# tree.net
KiCad netlist of a schematic drawn in EAGLE
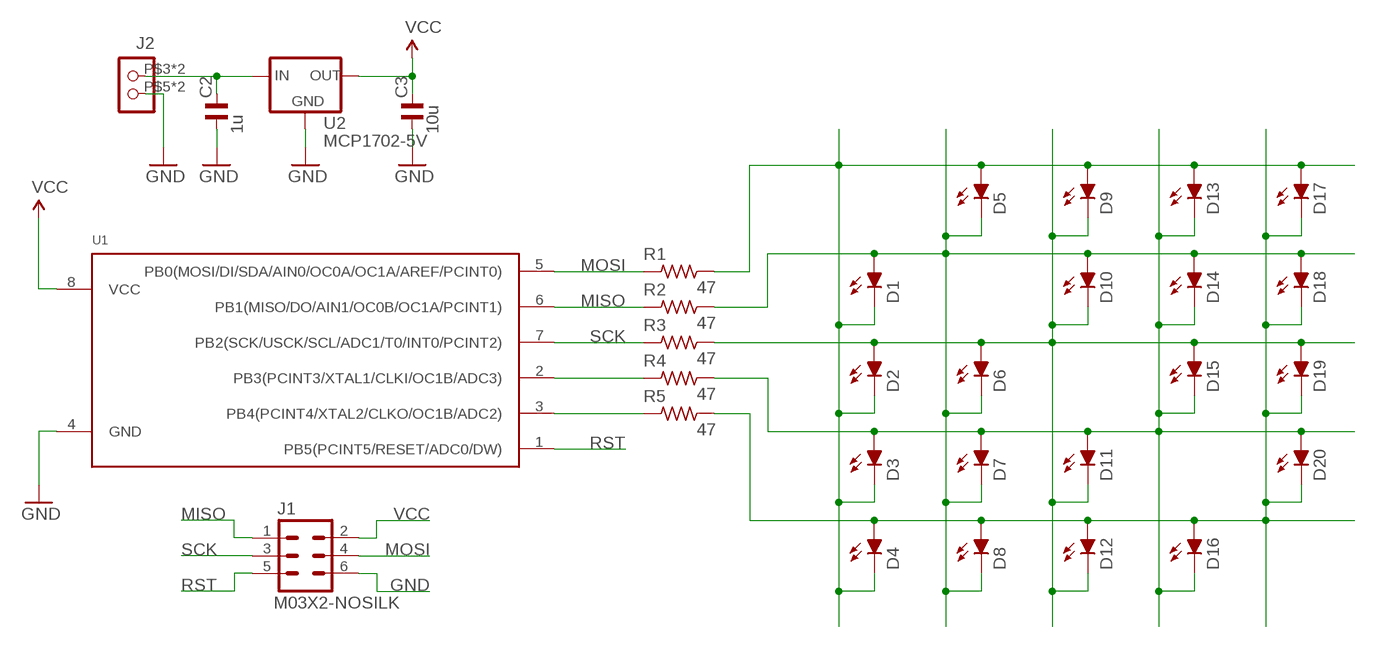
[diagram p0: schematic, sheet 1]

(export (version "E")
  (design (tool "Eeschema 10.0.6"))
  (components
    (comp (ref "C2")
      (value "1u")
      (footprint "eagle-import:C0805NOSILK")
      (libsource (lib "eagle-import") (part "C_0805NOSILK"))
    )
    (comp (ref "C3")
      (value "10u")
      (footprint "eagle-import:C0805NOSILK")
      (libsource (lib "eagle-import") (part "C_0805NOSILK"))
    )
    (comp (ref "D1")
      (value "LEDCHIP-LED0805NOSILK")
      (footprint "eagle-import:CHIP-LED0805NOSILK")
      (libsource (lib "eagle-import") (part "LEDCHIP-LED0805NOSILK"))
    )
    (comp (ref "D2")
      (value "LEDCHIP-LED0805NOSILK")
      (footprint "eagle-import:CHIP-LED0805NOSILK")
      (libsource (lib "eagle-import") (part "LEDCHIP-LED0805NOSILK"))
    )
    (comp (ref "D3")
      (value "LEDCHIP-LED0805NOSILK")
      (footprint "eagle-import:CHIP-LED0805NOSILK")
      (libsource (lib "eagle-import") (part "LEDCHIP-LED0805NOSILK"))
    )
    (comp (ref "D4")
      (value "LEDCHIP-LED0805NOSILK")
      (footprint "eagle-import:CHIP-LED0805NOSILK")
      (libsource (lib "eagle-import") (part "LEDCHIP-LED0805NOSILK"))
    )
    (comp (ref "D5")
      (value "LEDCHIP-LED0805NOSILK")
      (footprint "eagle-import:CHIP-LED0805NOSILK")
      (libsource (lib "eagle-import") (part "LEDCHIP-LED0805NOSILK"))
    )
    (comp (ref "D6")
      (value "LEDCHIP-LED0805NOSILK")
      (footprint "eagle-import:CHIP-LED0805NOSILK")
      (libsource (lib "eagle-import") (part "LEDCHIP-LED0805NOSILK"))
    )
    (comp (ref "D7")
      (value "LEDCHIP-LED0805NOSILK")
      (footprint "eagle-import:CHIP-LED0805NOSILK")
      (libsource (lib "eagle-import") (part "LEDCHIP-LED0805NOSILK"))
    )
    (comp (ref "D8")
      (value "LEDCHIP-LED0805NOSILK")
      (footprint "eagle-import:CHIP-LED0805NOSILK")
      (libsource (lib "eagle-import") (part "LEDCHIP-LED0805NOSILK"))
    )
    (comp (ref "D9")
      (value "LEDCHIP-LED0805NOSILK")
      (footprint "eagle-import:CHIP-LED0805NOSILK")
      (libsource (lib "eagle-import") (part "LEDCHIP-LED0805NOSILK"))
    )
    (comp (ref "D10")
      (value "LEDCHIP-LED0805NOSILK")
      (footprint "eagle-import:CHIP-LED0805NOSILK")
      (libsource (lib "eagle-import") (part "LEDCHIP-LED0805NOSILK"))
    )
    (comp (ref "D11")
      (value "LEDCHIP-LED0805NOSILK")
      (footprint "eagle-import:CHIP-LED0805NOSILK")
      (libsource (lib "eagle-import") (part "LEDCHIP-LED0805NOSILK"))
    )
    (comp (ref "D12")
      (value "LEDCHIP-LED0805NOSILK")
      (footprint "eagle-import:CHIP-LED0805NOSILK")
      (libsource (lib "eagle-import") (part "LEDCHIP-LED0805NOSILK"))
    )
    (comp (ref "D13")
      (value "LEDCHIP-LED0805NOSILK")
      (footprint "eagle-import:CHIP-LED0805NOSILK")
      (libsource (lib "eagle-import") (part "LEDCHIP-LED0805NOSILK"))
    )
    (comp (ref "D14")
      (value "LEDCHIP-LED0805NOSILK")
      (footprint "eagle-import:CHIP-LED0805NOSILK")
      (libsource (lib "eagle-import") (part "LEDCHIP-LED0805NOSILK"))
    )
    (comp (ref "D15")
      (value "LEDCHIP-LED0805NOSILK")
      (footprint "eagle-import:CHIP-LED0805NOSILK")
      (libsource (lib "eagle-import") (part "LEDCHIP-LED0805NOSILK"))
    )
    (comp (ref "D16")
      (value "LEDCHIP-LED0805NOSILK")
      (footprint "eagle-import:CHIP-LED0805NOSILK")
      (libsource (lib "eagle-import") (part "LEDCHIP-LED0805NOSILK"))
    )
    (comp (ref "D17")
      (value "LEDCHIP-LED0805NOSILK")
      (footprint "eagle-import:CHIP-LED0805NOSILK")
      (libsource (lib "eagle-import") (part "LEDCHIP-LED0805NOSILK"))
    )
    (comp (ref "D18")
      (value "LEDCHIP-LED0805NOSILK")
      (footprint "eagle-import:CHIP-LED0805NOSILK")
      (libsource (lib "eagle-import") (part "LEDCHIP-LED0805NOSILK"))
    )
    (comp (ref "D19")
      (value "LEDCHIP-LED0805NOSILK")
      (footprint "eagle-import:CHIP-LED0805NOSILK")
      (libsource (lib "eagle-import") (part "LEDCHIP-LED0805NOSILK"))
    )
    (comp (ref "D20")
      (value "LEDCHIP-LED0805NOSILK")
      (footprint "eagle-import:CHIP-LED0805NOSILK")
      (libsource (lib "eagle-import") (part "LEDCHIP-LED0805NOSILK"))
    )
    (comp (ref "J1")
      (value "M03X2-NOSILK")
      (footprint "eagle-import:2X03_LOCK_NOSILK")
      (libsource (lib "eagle-import") (part "M03X2-NOSILK"))
    )
    (comp (ref "J2")
      (value "CON_TERMINAL_HOLES")
      (footprint "eagle-import:TERMINAL_2P_4H")
      (libsource (lib "eagle-import") (part "CON_TERMINAL_HOLES"))
    )
    (comp (ref "R1")
      (value "47")
      (footprint "eagle-import:R0805NOSILK")
      (libsource (lib "eagle-import") (part "R_0805NOSILK"))
    )
    (comp (ref "R2")
      (value "47")
      (footprint "eagle-import:R0805NOSILK")
      (libsource (lib "eagle-import") (part "R_0805NOSILK"))
    )
    (comp (ref "R3")
      (value "47")
      (footprint "eagle-import:R0805NOSILK")
      (libsource (lib "eagle-import") (part "R_0805NOSILK"))
    )
    (comp (ref "R4")
      (value "47")
      (footprint "eagle-import:R0805NOSILK")
      (libsource (lib "eagle-import") (part "R_0805NOSILK"))
    )
    (comp (ref "R5")
      (value "47")
      (footprint "eagle-import:R0805NOSILK")
      (libsource (lib "eagle-import") (part "R_0805NOSILK"))
    )
    (comp (ref "U1")
      (value "ATTINY5-20SU-NOSILK")
      (footprint "eagle-import:SOP8-8S2-NOSILK")
      (libsource (lib "eagle-import") (part "ATTINY5-20SU-NOSILK"))
    )
    (comp (ref "U2")
      (value "MCP1702-5V")
      (footprint "eagle-import:SOT23_NOSILK")
      (libsource (lib "eagle-import") (part "V_REG_MCP170X-CB-NOSILK"))
    )
  )
  (nets
    (net (code "1") (name "/MISO") (class "Default")
      (node (ref "J1") (pin "1") (pinfunction "1_1") (pintype "passive"))
      (node (ref "R2") (pin "1") (pinfunction "1_1") (pintype "passive"))
      (node (ref "U1") (pin "6") (pinfunction "PB1(MISO/DO/AIN1/OC0B/OC1A/PCINT1)_6") (pintype "bidirectional"))
    )
    (net (code "2") (name "/MOSI") (class "Default")
      (node (ref "J1") (pin "4") (pinfunction "4_4") (pintype "passive"))
      (node (ref "R1") (pin "1") (pinfunction "1_1") (pintype "passive"))
      (node (ref "U1") (pin "5") (pinfunction "PB0(MOSI/DI/SDA/AIN0/OC0A/OC1A/AREF/PCINT0)_5") (pintype "bidirectional"))
    )
    (net (code "3") (name "/RST") (class "Default")
      (node (ref "J1") (pin "5") (pinfunction "5_5") (pintype "passive"))
      (node (ref "U1") (pin "1") (pinfunction "PB5(PCINT5/RESET/ADC0/DW)_1") (pintype "bidirectional"))
    )
    (net (code "4") (name "/SCK") (class "Default")
      (node (ref "J1") (pin "3") (pinfunction "3_3") (pintype "passive"))
      (node (ref "R3") (pin "1") (pinfunction "1_1") (pintype "passive"))
      (node (ref "U1") (pin "7") (pinfunction "PB2(SCK/USCK/SCL/ADC1/T0/INT0/PCINT2)_7") (pintype "bidirectional"))
    )
    (net (code "5") (name "GND") (class "Default")
      (node (ref "C2") (pin "1") (pinfunction "1_1") (pintype "passive"))
      (node (ref "C3") (pin "1") (pinfunction "1_1") (pintype "passive"))
      (node (ref "J1") (pin "6") (pinfunction "6_6") (pintype "passive"))
      (node (ref "J2") (pin "P$5") (pinfunction "2_P$5") (pintype "passive"))
      (node (ref "J2") (pin "P$6") (pinfunction "2_P$6") (pintype "passive"))
      (node (ref "U1") (pin "4") (pinfunction "GND_4") (pintype "bidirectional"))
      (node (ref "U2") (pin "1") (pinfunction "GND_1") (pintype "input"))
    )
    (net (code "6") (name "Net-(D1-PadA)") (class "Default")
      (node (ref "D1") (pin "A") (pinfunction "A_A") (pintype "passive"))
      (node (ref "D10") (pin "A") (pinfunction "A_A") (pintype "passive"))
      (node (ref "D14") (pin "A") (pinfunction "A_A") (pintype "passive"))
      (node (ref "D18") (pin "A") (pinfunction "A_A") (pintype "passive"))
      (node (ref "D5") (pin "C") (pinfunction "C_C") (pintype "passive"))
      (node (ref "D6") (pin "C") (pinfunction "C_C") (pintype "passive"))
      (node (ref "D7") (pin "C") (pinfunction "C_C") (pintype "passive"))
      (node (ref "D8") (pin "C") (pinfunction "C_C") (pintype "passive"))
      (node (ref "R2") (pin "2") (pinfunction "2_2") (pintype "passive"))
    )
    (net (code "7") (name "Net-(D1-PadC)") (class "Default")
      (node (ref "D1") (pin "C") (pinfunction "C_C") (pintype "passive"))
      (node (ref "D13") (pin "A") (pinfunction "A_A") (pintype "passive"))
      (node (ref "D17") (pin "A") (pinfunction "A_A") (pintype "passive"))
      (node (ref "D2") (pin "C") (pinfunction "C_C") (pintype "passive"))
      (node (ref "D3") (pin "C") (pinfunction "C_C") (pintype "passive"))
      (node (ref "D4") (pin "C") (pinfunction "C_C") (pintype "passive"))
      (node (ref "D5") (pin "A") (pinfunction "A_A") (pintype "passive"))
      (node (ref "D9") (pin "A") (pinfunction "A_A") (pintype "passive"))
      (node (ref "R1") (pin "2") (pinfunction "2_2") (pintype "passive"))
    )
    (net (code "8") (name "Net-(D10-PadC)") (class "Default")
      (node (ref "D10") (pin "C") (pinfunction "C_C") (pintype "passive"))
      (node (ref "D11") (pin "C") (pinfunction "C_C") (pintype "passive"))
      (node (ref "D12") (pin "C") (pinfunction "C_C") (pintype "passive"))
      (node (ref "D15") (pin "A") (pinfunction "A_A") (pintype "passive"))
      (node (ref "D19") (pin "A") (pinfunction "A_A") (pintype "passive"))
      (node (ref "D2") (pin "A") (pinfunction "A_A") (pintype "passive"))
      (node (ref "D6") (pin "A") (pinfunction "A_A") (pintype "passive"))
      (node (ref "D9") (pin "C") (pinfunction "C_C") (pintype "passive"))
      (node (ref "R3") (pin "2") (pinfunction "2_2") (pintype "passive"))
    )
    (net (code "9") (name "Net-(D11-PadA)") (class "Default")
      (node (ref "D11") (pin "A") (pinfunction "A_A") (pintype "passive"))
      (node (ref "D13") (pin "C") (pinfunction "C_C") (pintype "passive"))
      (node (ref "D14") (pin "C") (pinfunction "C_C") (pintype "passive"))
      (node (ref "D15") (pin "C") (pinfunction "C_C") (pintype "passive"))
      (node (ref "D16") (pin "C") (pinfunction "C_C") (pintype "passive"))
      (node (ref "D20") (pin "A") (pinfunction "A_A") (pintype "passive"))
      (node (ref "D3") (pin "A") (pinfunction "A_A") (pintype "passive"))
      (node (ref "D7") (pin "A") (pinfunction "A_A") (pintype "passive"))
      (node (ref "R4") (pin "2") (pinfunction "2_2") (pintype "passive"))
    )
    (net (code "10") (name "Net-(D12-PadA)") (class "Default")
      (node (ref "D12") (pin "A") (pinfunction "A_A") (pintype "passive"))
      (node (ref "D16") (pin "A") (pinfunction "A_A") (pintype "passive"))
      (node (ref "D17") (pin "C") (pinfunction "C_C") (pintype "passive"))
      (node (ref "D18") (pin "C") (pinfunction "C_C") (pintype "passive"))
      (node (ref "D19") (pin "C") (pinfunction "C_C") (pintype "passive"))
      (node (ref "D20") (pin "C") (pinfunction "C_C") (pintype "passive"))
      (node (ref "D4") (pin "A") (pinfunction "A_A") (pintype "passive"))
      (node (ref "D8") (pin "A") (pinfunction "A_A") (pintype "passive"))
      (node (ref "R5") (pin "2") (pinfunction "2_2") (pintype "passive"))
    )
    (net (code "11") (name "Net-(U1-PB3(PCINT3{slash}XTAL1{slash}CLKI{slash}OC1B{slash}ADC3))") (class "Default")
      (node (ref "R4") (pin "1") (pinfunction "1_1") (pintype "passive"))
      (node (ref "U1") (pin "2") (pinfunction "PB3(PCINT3/XTAL1/CLKI/OC1B/ADC3)_2") (pintype "bidirectional"))
    )
    (net (code "12") (name "Net-(U1-PB4(PCINT4{slash}XTAL2{slash}CLKO{slash}OC1B{slash}ADC2))") (class "Default")
      (node (ref "R5") (pin "1") (pinfunction "1_1") (pintype "passive"))
      (node (ref "U1") (pin "3") (pinfunction "PB4(PCINT4/XTAL2/CLKO/OC1B/ADC2)_3") (pintype "bidirectional"))
    )
    (net (code "13") (name "Net-(U2-IN)") (class "Default")
      (node (ref "C2") (pin "2") (pinfunction "2_2") (pintype "passive"))
      (node (ref "J2") (pin "P$3") (pinfunction "1_P$3") (pintype "passive"))
      (node (ref "J2") (pin "P$4") (pinfunction "1_P$4") (pintype "passive"))
      (node (ref "U2") (pin "3") (pinfunction "IN_3") (pintype "input"))
    )
    (net (code "14") (name "VCC") (class "Default")
      (node (ref "C3") (pin "2") (pinfunction "2_2") (pintype "passive"))
      (node (ref "J1") (pin "2") (pinfunction "2_2") (pintype "passive"))
      (node (ref "U1") (pin "8") (pinfunction "VCC_8") (pintype "bidirectional"))
      (node (ref "U2") (pin "2") (pinfunction "OUT_2") (pintype "power_in"))
    )
  )
)
